# 05_CONNECTORS.net
KiCad netlist of a schematic drawn in Altium Designer
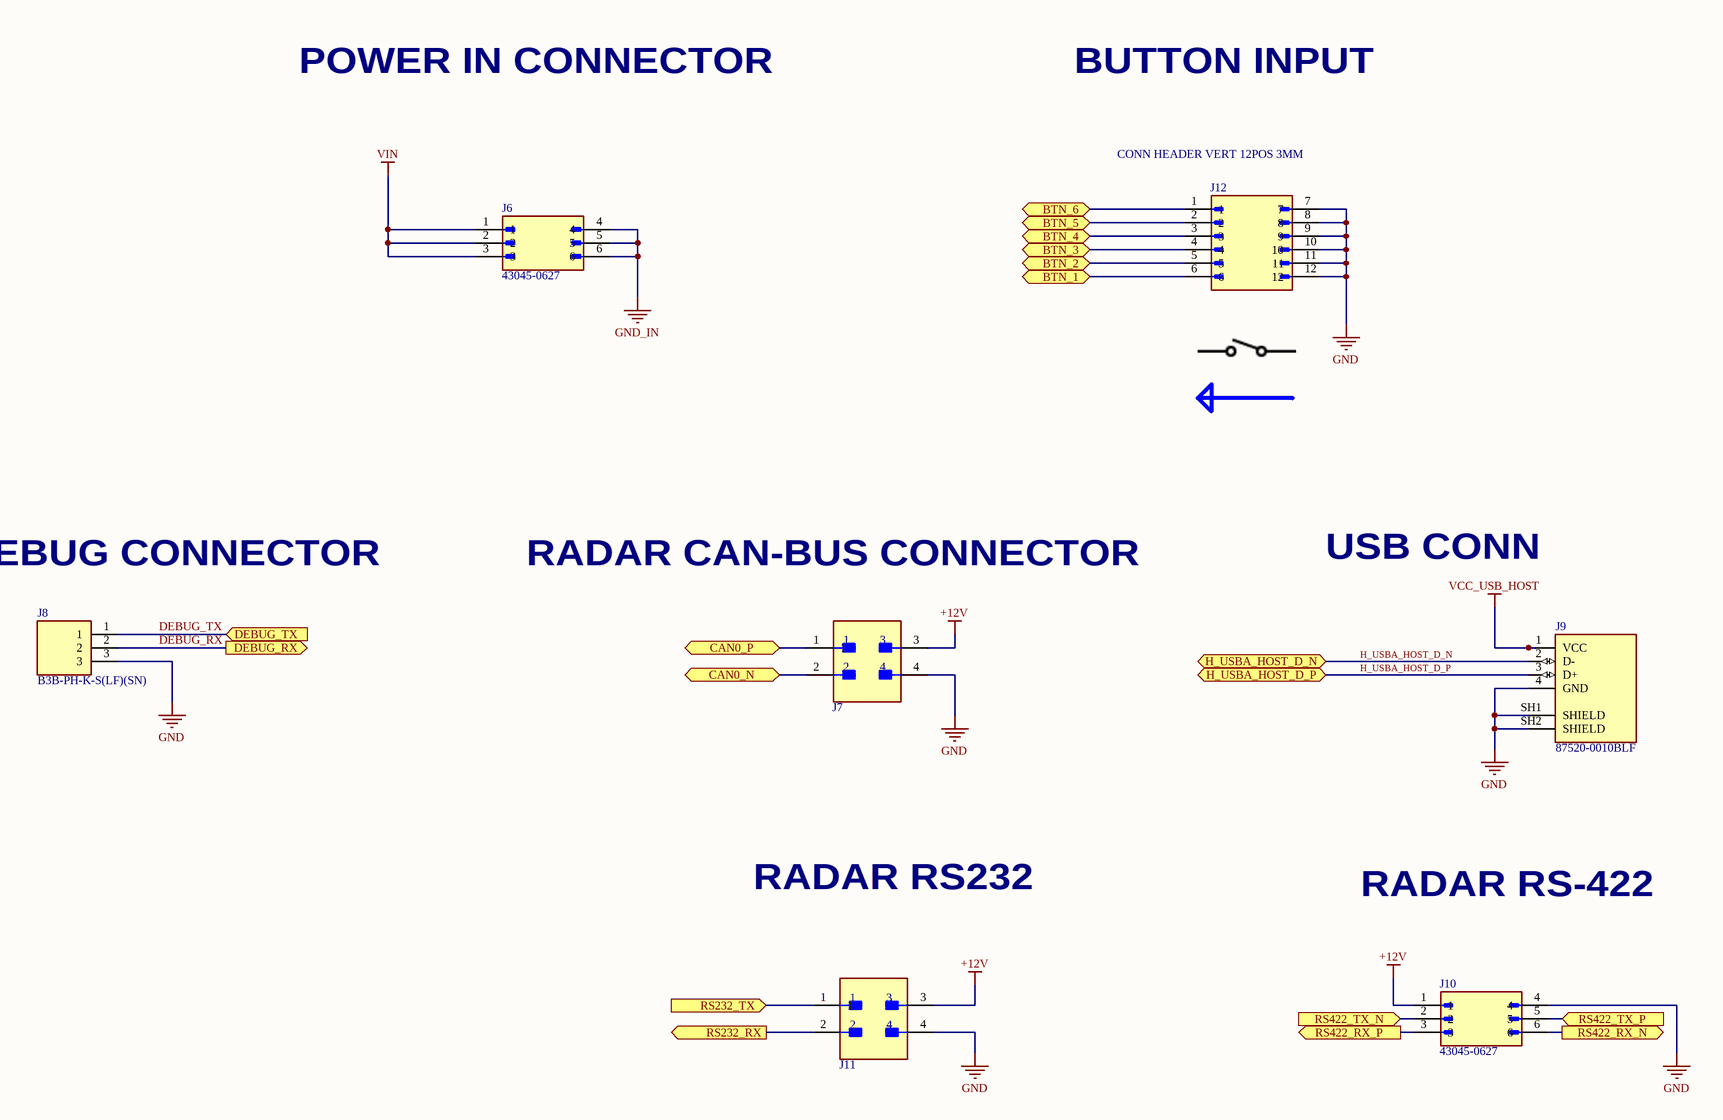
[diagram p0: 05_CONNECTORS.SchDoc]

(export (version "E")
  (design (tool "Eeschema 10.0.6"))
  (components
    (comp (ref "J6")
      (value "43045-0627")
      (footprint "MOLEX_430450627")
      (description "Conn Wire to Board HDR 6 POS 3mm Solder ST Thru-Hole Micro-Fit 3.0™ Tray")
      (fields (field (name "MANUFACTURER") "Molex"))
      (libsource (lib "HW_HOLLAND_NCDM_MONITOR_R1") (part "43045-0627"))
    )
    (comp (ref "J7")
      (value "0430450427")
      (footprint "MicroFit_2x2_VERT")
      (description "Connector Header Through Hole 4 position 0.118\" (3.00mm)")
      (fields (field (name "MANUFACTURER") "Molex"))
      (libsource (lib "HW_HOLLAND_NCDM_MONITOR_R1") (part "MicroFit_2x2_VERT"))
    )
    (comp (ref "J8")
      (value "B3B-PH-K-S(LF)(SN)")
      (footprint "SHDR3W50P0X200_1X3_790X450X600P")
      (description "Connector")
      (fields (field (name "LCSC PART NUMBER") "C131339"))
      (libsource (lib "HW_HOLLAND_NCDM_MONITOR_R1") (part "B3B-PH-K-S_LF__SN_"))
    )
    (comp (ref "J9")
      (value "87520-0010BLF")
      (footprint "AMPHENOL_87520-0010BLF")
      (fields (field (name "MANUFACTURER") "Amphenol ICC / FCI"))
      (libsource (lib "HW_HOLLAND_NCDM_MONITOR_R1") (part "87520-0010BLF"))
    )
    (comp (ref "J10")
      (value "43045-0627")
      (footprint "MOLEX_430450627")
      (description "Conn Wire to Board HDR 6 POS 3mm Solder ST Thru-Hole Micro-Fit 3.0™ Tray")
      (fields (field (name "MANUFACTURER") "Molex"))
      (libsource (lib "HW_HOLLAND_NCDM_MONITOR_R1") (part "43045-0627"))
    )
    (comp (ref "J11")
      (value "0430450427")
      (footprint "MicroFit_2x2_VERT")
      (description "Connector Header Through Hole 4 position 0.118\" (3.00mm)")
      (fields (field (name "MANUFACTURER") "Molex"))
      (libsource (lib "HW_HOLLAND_NCDM_MONITOR_R1") (part "MicroFit_2x2_VERT"))
    )
    (comp (ref "J12")
      (value "CONN HEADER VERT 12POS 3MM")
      (footprint "MOLEX_430451227")
      (description "Conn Power HDR 12 POS 3mm Solder ST Thru-Hole 12 Terminal 1 Port Micro-Fit 3.0™ Frame")
      (fields (field (name "MANUFACTURER") "Molex") (field (name "MANUFACTURER PART NUMBER") "43045-1227"))
      (libsource (lib "HW_HOLLAND_NCDM_MONITOR_R1") (part "43045-1227"))
    )
  )
  (nets
    (net (code "1") (name "+12V") (class "Default")
      (node (ref "J10") (pin "1") (pinfunction "1_1") (pintype "passive"))
      (node (ref "J11") (pin "3") (pinfunction "3_3") (pintype "passive"))
      (node (ref "J7") (pin "3") (pinfunction "3_3") (pintype "passive"))
    )
    (net (code "2") (name "/BTN_1") (class "Default")
      (node (ref "J12") (pin "6") (pinfunction "6_6") (pintype "passive"))
    )
    (net (code "3") (name "/BTN_2") (class "Default")
      (node (ref "J12") (pin "5") (pinfunction "5_5") (pintype "passive"))
    )
    (net (code "4") (name "/BTN_3") (class "Default")
      (node (ref "J12") (pin "4") (pinfunction "4_4") (pintype "passive"))
    )
    (net (code "5") (name "/BTN_4") (class "Default")
      (node (ref "J12") (pin "3") (pinfunction "3_3") (pintype "passive"))
    )
    (net (code "6") (name "/BTN_5") (class "Default")
      (node (ref "J12") (pin "2") (pinfunction "2_2") (pintype "passive"))
    )
    (net (code "7") (name "/BTN_6") (class "Default")
      (node (ref "J12") (pin "1") (pinfunction "1_1") (pintype "passive"))
    )
    (net (code "8") (name "/CAN0_N") (class "Default")
      (node (ref "J7") (pin "2") (pinfunction "2_2") (pintype "passive"))
    )
    (net (code "9") (name "/CAN0_P") (class "Default")
      (node (ref "J7") (pin "1") (pinfunction "1_1") (pintype "passive"))
    )
    (net (code "10") (name "/DEBUG_RX") (class "Default")
      (node (ref "J8") (pin "2") (pinfunction "2_2") (pintype "passive"))
    )
    (net (code "11") (name "/DEBUG_TX") (class "Default")
      (node (ref "J8") (pin "1") (pinfunction "1_1") (pintype "passive"))
    )
    (net (code "12") (name "/H_USBA_HOST_D_N") (class "Default")
      (node (ref "J9") (pin "2") (pinfunction "D-_2") (pintype "bidirectional"))
    )
    (net (code "13") (name "/H_USBA_HOST_D_P") (class "Default")
      (node (ref "J9") (pin "3") (pinfunction "D+_3") (pintype "bidirectional"))
    )
    (net (code "14") (name "/RS232_RX") (class "Default")
      (node (ref "J11") (pin "2") (pinfunction "2_2") (pintype "passive"))
    )
    (net (code "15") (name "/RS232_TX") (class "Default")
      (node (ref "J11") (pin "1") (pinfunction "1_1") (pintype "passive"))
    )
    (net (code "16") (name "/RS422_RX_N") (class "Default")
      (node (ref "J10") (pin "6") (pinfunction "6_6") (pintype "passive"))
    )
    (net (code "17") (name "/RS422_RX_P") (class "Default")
      (node (ref "J10") (pin "3") (pinfunction "3_3") (pintype "passive"))
    )
    (net (code "18") (name "/RS422_TX_N") (class "Default")
      (node (ref "J10") (pin "2") (pinfunction "2_2") (pintype "passive"))
    )
    (net (code "19") (name "/RS422_TX_P") (class "Default")
      (node (ref "J10") (pin "5") (pinfunction "5_5") (pintype "passive"))
    )
    (net (code "20") (name "GND") (class "Default")
      (node (ref "J10") (pin "4") (pinfunction "4_4") (pintype "passive"))
      (node (ref "J11") (pin "4") (pinfunction "4_4") (pintype "passive"))
      (node (ref "J12") (pin "10") (pinfunction "10_10") (pintype "passive"))
      (node (ref "J12") (pin "11") (pinfunction "11_11") (pintype "passive"))
      (node (ref "J12") (pin "12") (pinfunction "12_12") (pintype "passive"))
      (node (ref "J12") (pin "7") (pinfunction "7_7") (pintype "passive"))
      (node (ref "J12") (pin "8") (pinfunction "8_8") (pintype "passive"))
      (node (ref "J12") (pin "9") (pinfunction "9_9") (pintype "passive"))
      (node (ref "J7") (pin "4") (pinfunction "4_4") (pintype "passive"))
      (node (ref "J8") (pin "3") (pinfunction "3_3") (pintype "passive"))
      (node (ref "J9") (pin "4") (pinfunction "GND_4") (pintype "passive"))
      (node (ref "J9") (pin "SH1") (pinfunction "SHIELD_SH1") (pintype "passive"))
      (node (ref "J9") (pin "SH2") (pinfunction "SHIELD_SH2") (pintype "passive"))
    )
    (net (code "21") (name "GND_IN") (class "Default")
      (node (ref "J6") (pin "4") (pinfunction "4_4") (pintype "passive"))
      (node (ref "J6") (pin "5") (pinfunction "5_5") (pintype "passive"))
      (node (ref "J6") (pin "6") (pinfunction "6_6") (pintype "passive"))
    )
    (net (code "22") (name "VCC_USB_HOST") (class "Default")
      (node (ref "J9") (pin "1") (pinfunction "VCC_1") (pintype "power_in"))
    )
    (net (code "23") (name "VIN") (class "Default")
      (node (ref "J6") (pin "1") (pinfunction "1_1") (pintype "passive"))
      (node (ref "J6") (pin "2") (pinfunction "2_2") (pintype "passive"))
      (node (ref "J6") (pin "3") (pinfunction "3_3") (pintype "passive"))
    )
  )
)
